# Connectors.net
KiCad netlist of a schematic drawn in Altium Designer
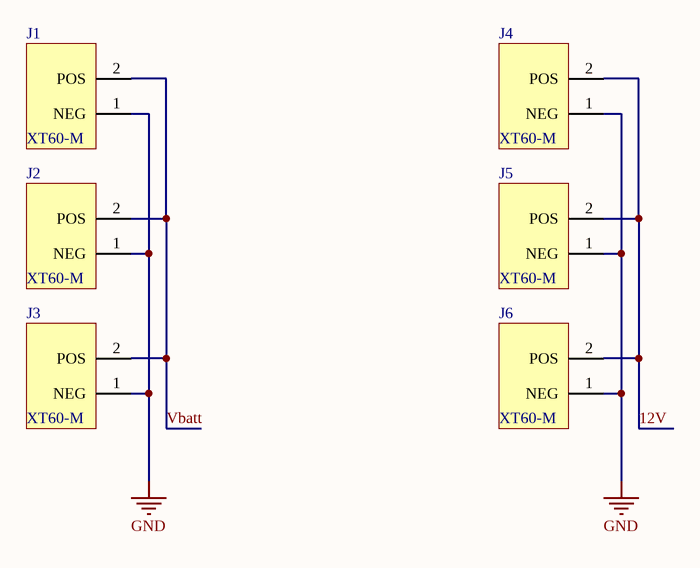
[diagram p0: Connectors.SchDoc]

(export (version "E")
  (design (tool "Eeschema 10.0.6"))
  (components
    (comp (ref "J1")
      (value "XT60-M")
      (footprint "*AMASS_XT60-M")
      (description "Plug; DC supply; XT60; male; PIN: 2; for cable; soldered; 30A; 500V")
      (fields (field (name "MF") "AMASS"))
      (libsource (lib "XT60-M") (part "XT60-M"))
    )
    (comp (ref "J2")
      (value "XT60-M")
      (footprint "*AMASS_XT60-M")
      (description "Plug; DC supply; XT60; male; PIN: 2; for cable; soldered; 30A; 500V")
      (fields (field (name "MF") "AMASS"))
      (libsource (lib "XT60-M") (part "XT60-M"))
    )
    (comp (ref "J3")
      (value "XT60-M")
      (footprint "*AMASS_XT60-M")
      (description "Plug; DC supply; XT60; male; PIN: 2; for cable; soldered; 30A; 500V")
      (fields (field (name "MF") "AMASS"))
      (libsource (lib "XT60-M") (part "XT60-M"))
    )
    (comp (ref "J4")
      (value "XT60-M")
      (footprint "*AMASS_XT60-M")
      (description "Plug; DC supply; XT60; male; PIN: 2; for cable; soldered; 30A; 500V")
      (fields (field (name "MF") "AMASS"))
      (libsource (lib "XT60-M") (part "XT60-M"))
    )
    (comp (ref "J5")
      (value "XT60-M")
      (footprint "*AMASS_XT60-M")
      (description "Plug; DC supply; XT60; male; PIN: 2; for cable; soldered; 30A; 500V")
      (fields (field (name "MF") "AMASS"))
      (libsource (lib "XT60-M") (part "XT60-M"))
    )
    (comp (ref "J6")
      (value "XT60-M")
      (footprint "*AMASS_XT60-M")
      (description "Plug; DC supply; XT60; male; PIN: 2; for cable; soldered; 30A; 500V")
      (fields (field (name "MF") "AMASS"))
      (libsource (lib "XT60-M") (part "XT60-M"))
    )
  )
  (nets
    (net (code "1") (name "/12V") (class "Default")
      (node (ref "J4") (pin "2") (pinfunction "POS_2") (pintype "passive"))
      (node (ref "J5") (pin "2") (pinfunction "POS_2") (pintype "passive"))
      (node (ref "J6") (pin "2") (pinfunction "POS_2") (pintype "passive"))
    )
    (net (code "2") (name "/Vbatt") (class "Default")
      (node (ref "J1") (pin "2") (pinfunction "POS_2") (pintype "passive"))
      (node (ref "J2") (pin "2") (pinfunction "POS_2") (pintype "passive"))
      (node (ref "J3") (pin "2") (pinfunction "POS_2") (pintype "passive"))
    )
    (net (code "3") (name "GND") (class "Default")
      (node (ref "J1") (pin "1") (pinfunction "NEG_1") (pintype "passive"))
      (node (ref "J2") (pin "1") (pinfunction "NEG_1") (pintype "passive"))
      (node (ref "J3") (pin "1") (pinfunction "NEG_1") (pintype "passive"))
      (node (ref "J4") (pin "1") (pinfunction "NEG_1") (pintype "passive"))
      (node (ref "J5") (pin "1") (pinfunction "NEG_1") (pintype "passive"))
      (node (ref "J6") (pin "1") (pinfunction "NEG_1") (pintype "passive"))
    )
  )
)
